# driver_isolated_trans.net
KiCad netlist of a schematic drawn in Altium Designer
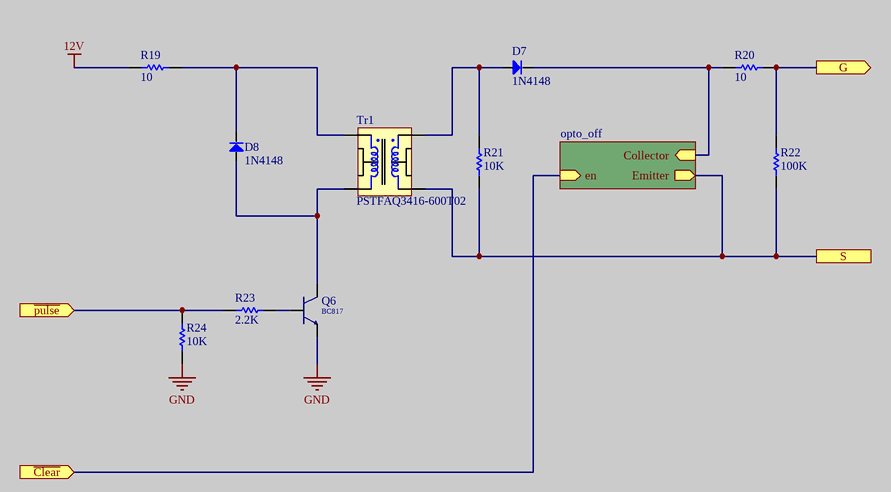
[diagram p0: driver_isolated_trans.SchDoc]

(export (version "E")
  (design (tool "Eeschema 10.0.6"))
  (components
    (comp (ref "D7")
      (value "1N4148")
      (footprint "FastDiode")
      (description "FastDiode")
      (fields (field (name "PUBLISHER") "Altium Limited"))
      (libsource (lib "eLIB") (part "FastDiode"))
    )
    (comp (ref "D8")
      (value "1N4148")
      (footprint "FastDiode")
      (description "FastDiode")
      (fields (field (name "PUBLISHER") "Altium Limited"))
      (libsource (lib "eLIB") (part "FastDiode"))
    )
    (comp (ref "Q6")
      (value "NPN transistor")
      (footprint "NPN")
      (description "45 V, 0.5 A")
      (fields (field (name "TRANSISTOR") "BC817"))
      (libsource (lib "eLIB") (part "BC817"))
    )
    (comp (ref "R19")
      (value "10")
      (footprint "RESC0603")
      (description "0603,0.1W")
      (fields (field (name "PUBLISHER") "Altium Limited"))
      (libsource (lib "eLIB") (part "Resistor"))
    )
    (comp (ref "R20")
      (value "10")
      (footprint "RESC0603")
      (description "0603,0.1W")
      (fields (field (name "PUBLISHER") "Altium Limited"))
      (libsource (lib "eLIB") (part "Resistor"))
    )
    (comp (ref "R21")
      (value "10K")
      (footprint "RESC0603")
      (description "0603,0.1W")
      (fields (field (name "PUBLISHER") "Altium Limited"))
      (libsource (lib "eLIB") (part "Resistor"))
    )
    (comp (ref "R22")
      (value "100K")
      (footprint "RESC0603")
      (description "0603,0.1W")
      (fields (field (name "PUBLISHER") "Altium Limited"))
      (libsource (lib "eLIB") (part "Resistor"))
    )
    (comp (ref "R23")
      (value "2.2K")
      (footprint "RESC0603")
      (description "0603,0.1W")
      (fields (field (name "PUBLISHER") "Altium Limited"))
      (libsource (lib "eLIB") (part "Resistor"))
    )
    (comp (ref "R24")
      (value "10K")
      (footprint "RESC0603")
      (description "0603,0.1W")
      (fields (field (name "PUBLISHER") "Altium Limited"))
      (libsource (lib "eLIB") (part "Resistor"))
    )
    (comp (ref "Tr1")
      (value "PSTFAQ3416-600T02")
      (footprint "PSTFAQ3416-600T020")
      (fields (field (name "MANF") "OMRON") (field (name "MANF_P#") "G8QN-1C4 DC12"))
      (libsource (lib "eLIB") (part "transpulse small"))
    )
  )
  (nets
    (net (code "1") (name "/Collector") (class "Default")
      (node (ref "D7") (pin "2") (pinfunction "K_2") (pintype "passive"))
      (node (ref "R20") (pin "2") (pinfunction "2_2") (pintype "passive"))
    )
    (net (code "2") (name "/G") (class "Default")
      (node (ref "R20") (pin "1") (pinfunction "1_1") (pintype "passive"))
      (node (ref "R22") (pin "2") (pinfunction "2_2") (pintype "passive"))
    )
    (net (code "3") (name "/S") (class "Default")
      (node (ref "R21") (pin "1") (pinfunction "1_1") (pintype "passive"))
      (node (ref "R22") (pin "1") (pinfunction "1_1") (pintype "passive"))
      (node (ref "Tr1") (pin "3") (pinfunction "3_3") (pintype "passive"))
    )
    (net (code "5") (name "/~{pulse}") (class "Default")
      (node (ref "R23") (pin "2") (pinfunction "2_2") (pintype "passive"))
      (node (ref "R24") (pin "1") (pinfunction "1_1") (pintype "passive"))
    )
    (net (code "6") (name "12V") (class "Default")
      (node (ref "R19") (pin "2") (pinfunction "2_2") (pintype "passive"))
    )
    (net (code "7") (name "GND") (class "Default")
      (node (ref "Q6") (pin "2") (pinfunction "E_2") (pintype "passive"))
      (node (ref "R24") (pin "2") (pinfunction "2_2") (pintype "passive"))
    )
    (net (code "8") (name "Net-(D7-A)") (class "Default")
      (node (ref "D7") (pin "1") (pinfunction "A_1") (pintype "passive"))
      (node (ref "R21") (pin "2") (pinfunction "2_2") (pintype "passive"))
      (node (ref "Tr1") (pin "4") (pinfunction "4_4") (pintype "passive"))
    )
    (net (code "9") (name "Net-(D8-A)") (class "Default")
      (node (ref "D8") (pin "1") (pinfunction "A_1") (pintype "passive"))
      (node (ref "Q6") (pin "3") (pinfunction "C_3") (pintype "passive"))
      (node (ref "Tr1") (pin "2") (pinfunction "2_2") (pintype "passive"))
    )
    (net (code "10") (name "Net-(D8-K)") (class "Default")
      (node (ref "D8") (pin "2") (pinfunction "K_2") (pintype "passive"))
      (node (ref "R19") (pin "1") (pinfunction "1_1") (pintype "passive"))
      (node (ref "Tr1") (pin "1") (pinfunction "1_1") (pintype "passive"))
    )
    (net (code "11") (name "Net-(Q6-B)") (class "Default")
      (node (ref "Q6") (pin "1") (pinfunction "B_1") (pintype "passive"))
      (node (ref "R23") (pin "1") (pinfunction "1_1") (pintype "passive"))
    )
  )
)
